# Temp_sensor.net
KiCad netlist of a schematic drawn in Altium Designer
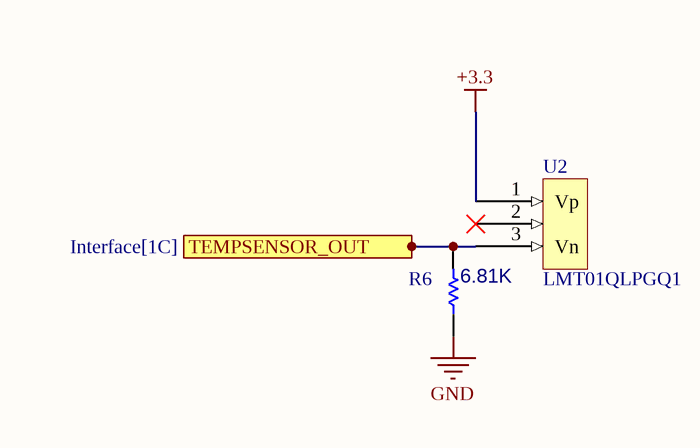
[diagram p0: Temp_sensor.SchDoc]

(export (version "E")
  (design (tool "Eeschema 10.0.6"))
  (components
    (comp (ref "R6")
      (value "6.81K")
      (footprint "R0603A")
      (description "Resistor")
      (libsource (lib "Space Concordia") (part "Resistor"))
    )
    (comp (ref "U2")
      (value "LMT01QLPGQ1")
      (footprint "LMT01-Q1")
      (description "Serial Switch/Digital Sensor, 13 Bit(s), 0.75Cel, Rectangular, Through Hole Mount")
      (libsource (lib "Space Concordia") (part "New symbol 1"))
    )
  )
  (nets
    (net (code "1") (name "+3.3") (class "Default")
      (node (ref "U2") (pin "1") (pinfunction "Vp_1") (pintype "input"))
    )
    (net (code "2") (name "/TEMPSENSOR_OUT") (class "Default")
      (node (ref "R6") (pin "2") (pinfunction "2_2") (pintype "passive"))
      (node (ref "U2") (pin "3") (pinfunction "Vn_3") (pintype "input"))
    )
    (net (code "3") (name "GND") (class "Default")
      (node (ref "R6") (pin "1") (pinfunction "1_1") (pintype "passive"))
    )
    (net (code "4") (name "unconnected-(U2-Pad2)") (class "Default")
      (node (ref "U2") (pin "2") (pintype "input+no_connect"))
    )
  )
)
